# aig2_power_cpu.net
KiCad netlist of a schematic drawn in Altium Designer
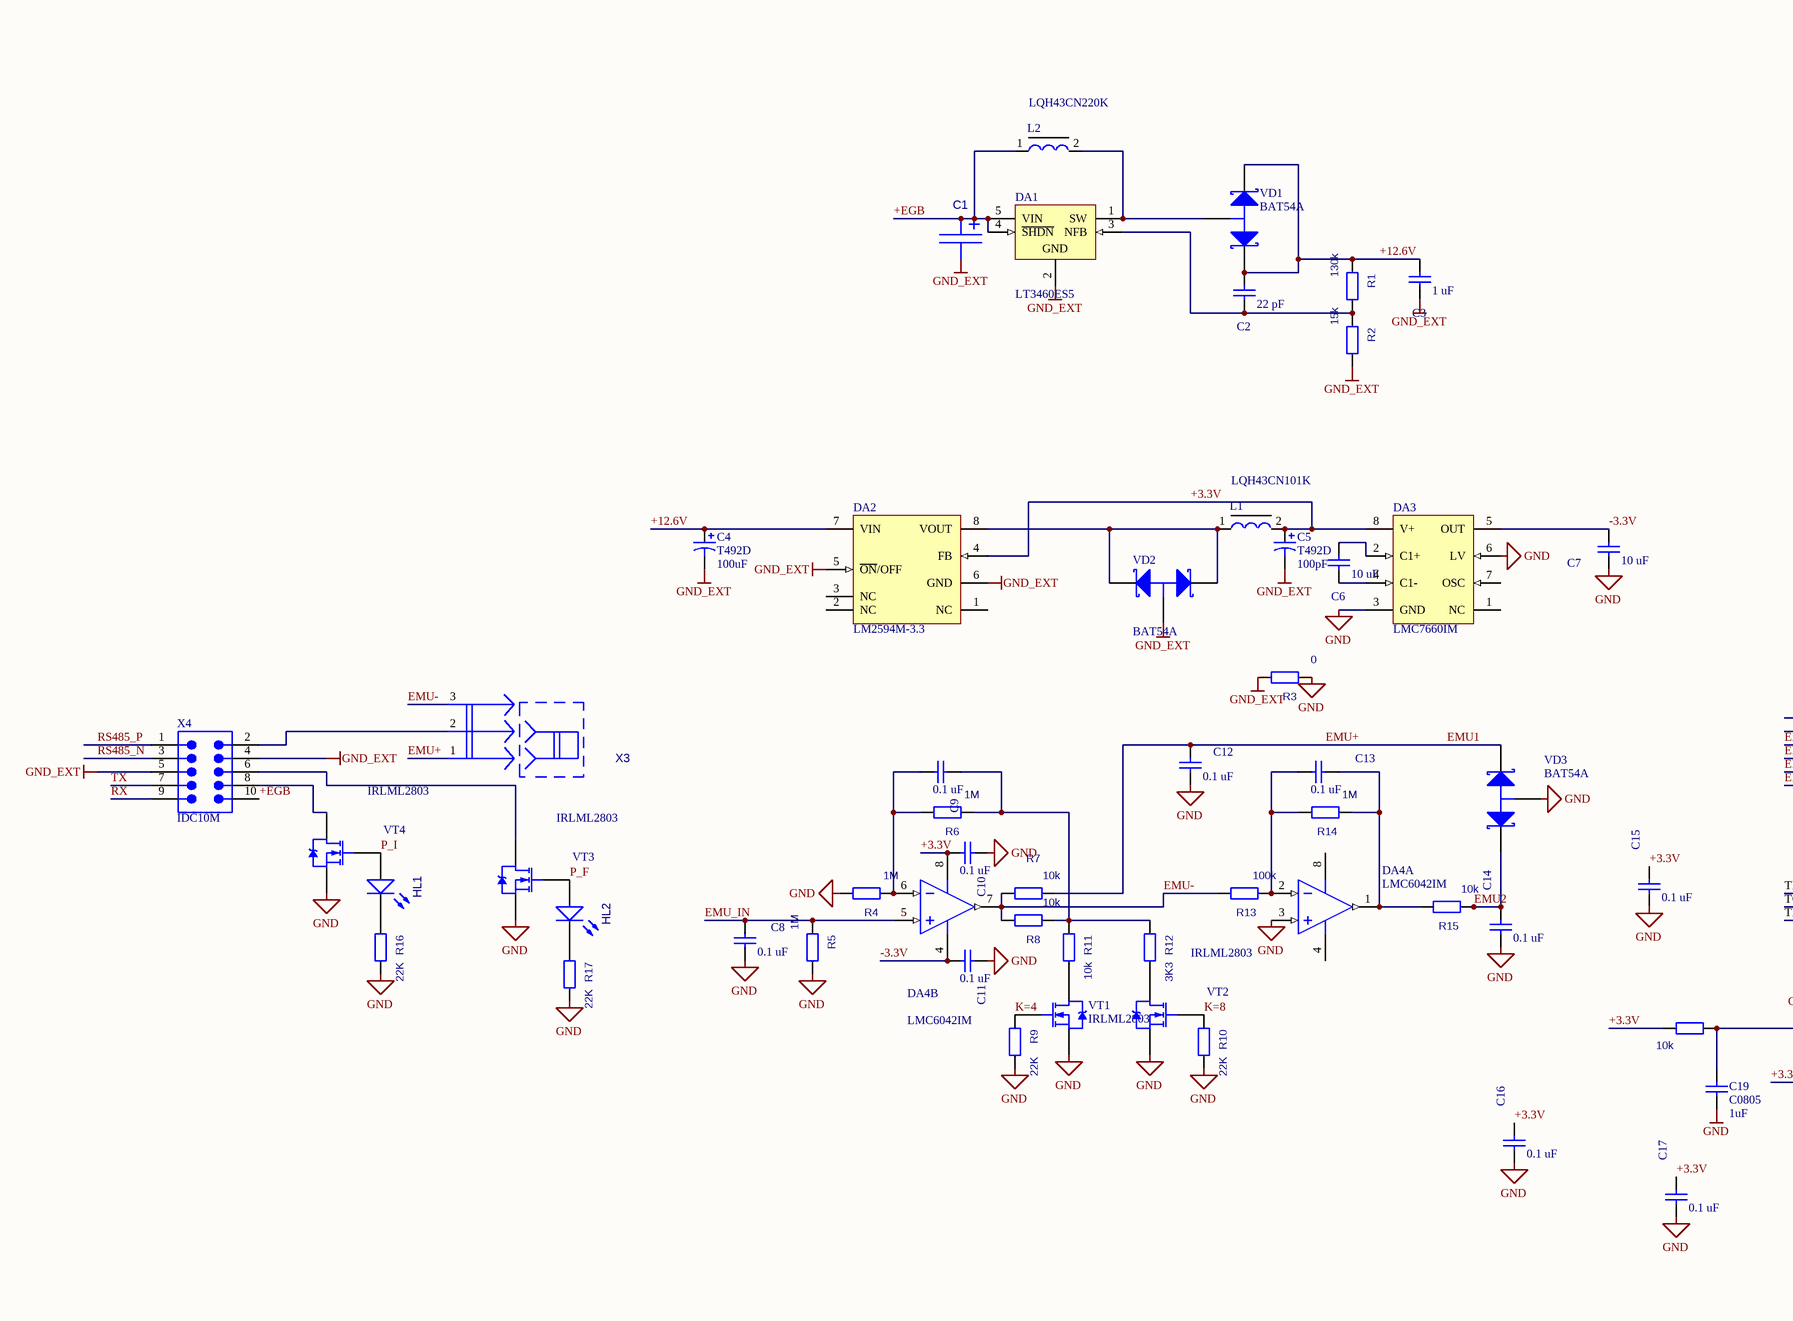
[diagram p0: aig2_power_cpu.SchDoc, left]
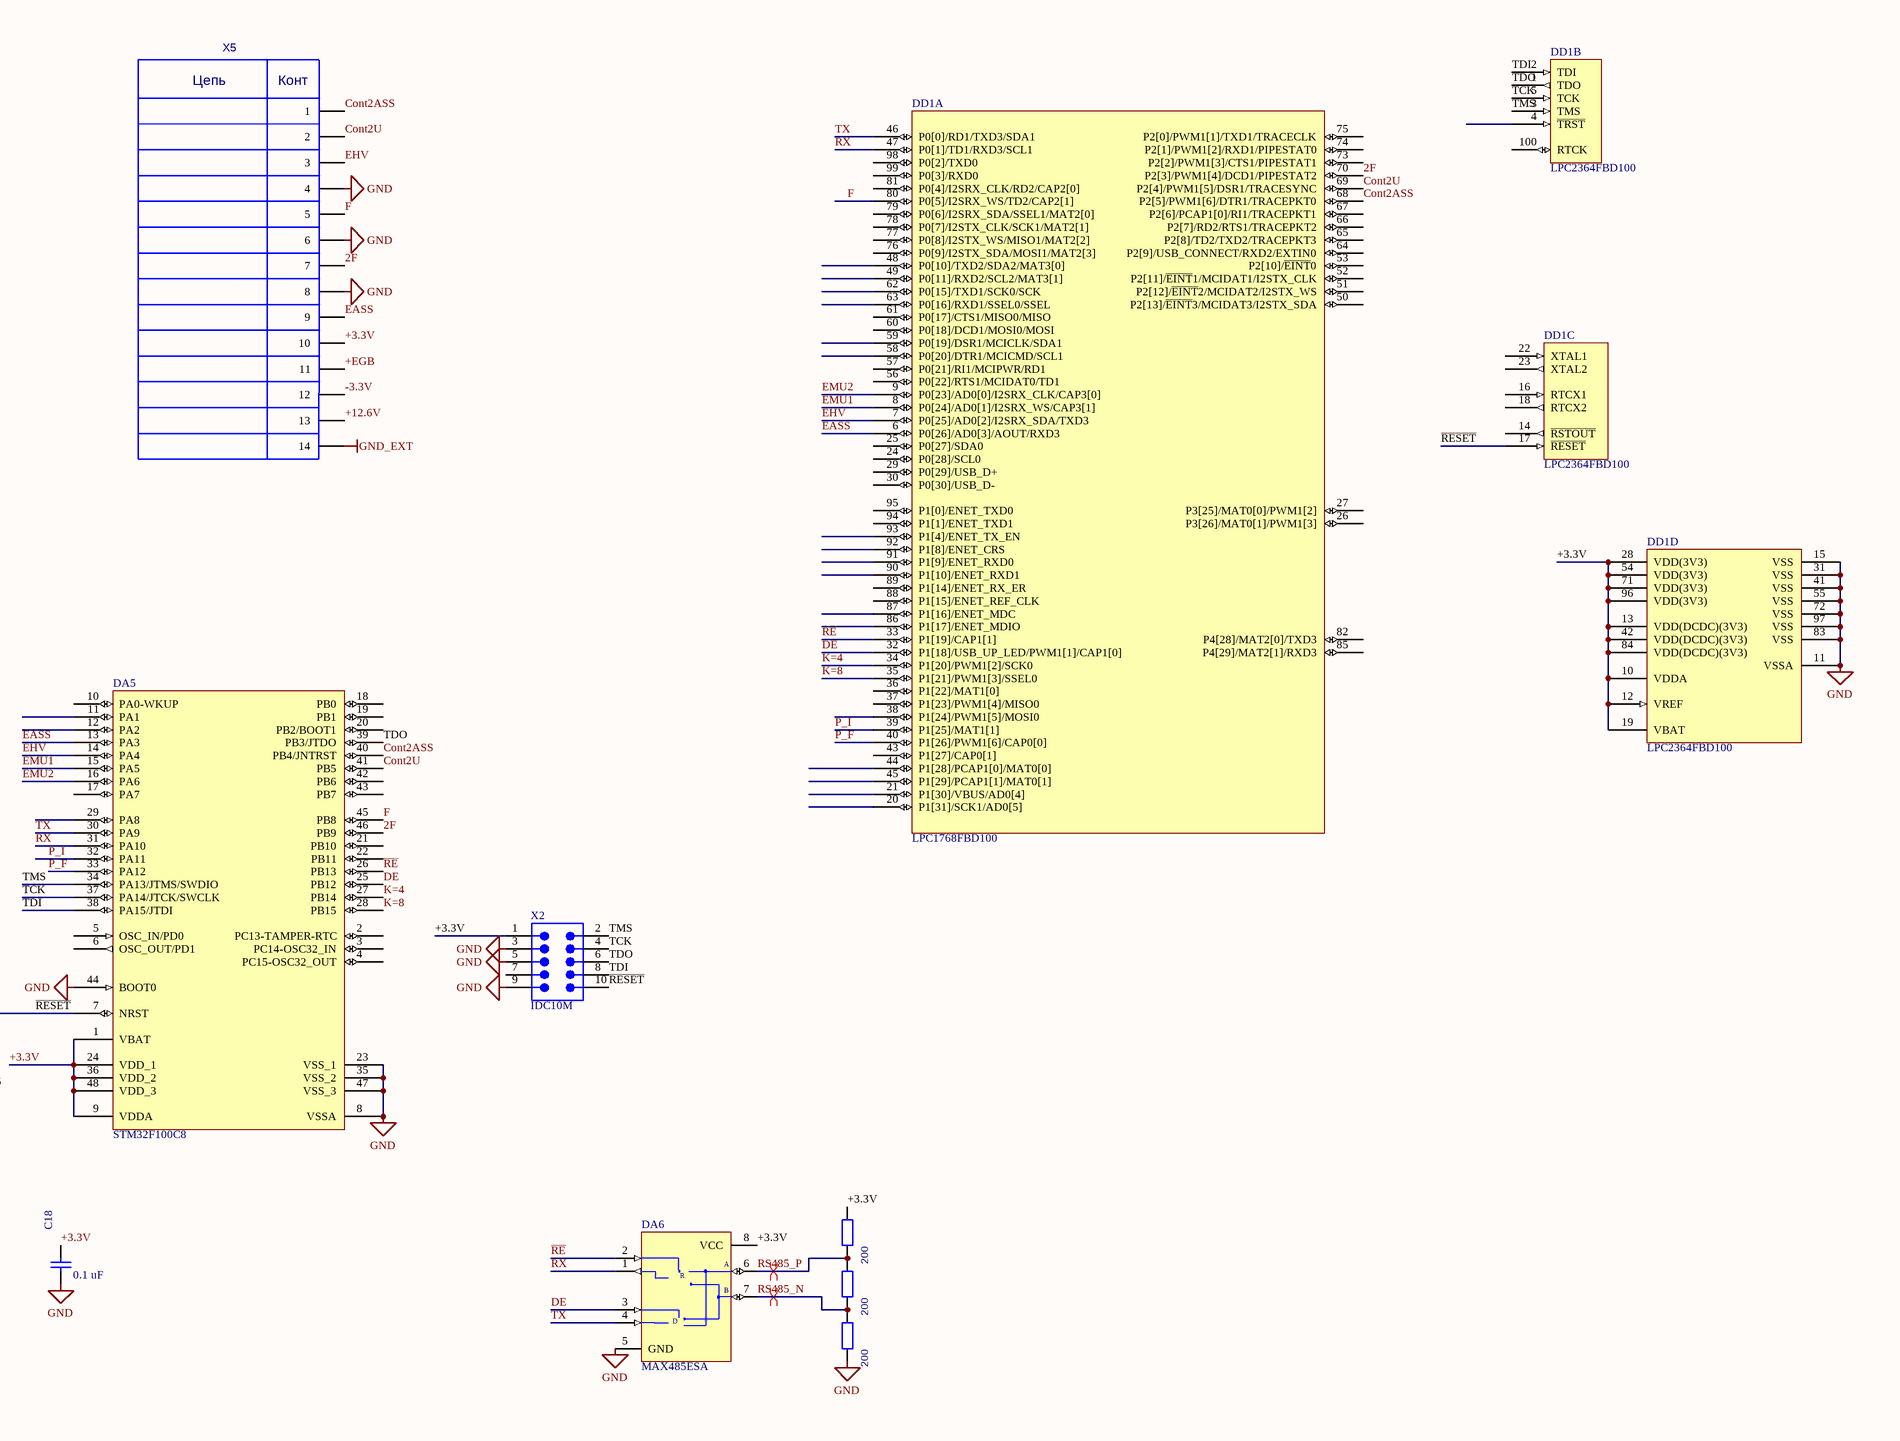
[diagram p1: aig2_power_cpu.SchDoc, right]

(export (version "E")
  (design (tool "Eeschema 10.0.6"))
  (components
    (comp (ref "C1")
      (value "CAPASITOR A")
      (footprint "CAPASITOR A")
      (libsource (lib "MyElements") (part "CAPASITOR A"))
    )
    (comp (ref "C2")
      (value "22 pF")
      (footprint "CC0805")
      (description "Ceramic Chip Capacitor - Standard")
      (fields (field (name "Comment") "C0805") (field (name "PUBLISHER") "Altium Limited"))
      (libsource (lib "KEMET Chip Capacitor") (part "C0805"))
    )
    (comp (ref "C3")
      (value "1 uF")
      (footprint "CC0805")
      (description "Ceramic Chip Capacitor - Standard")
      (fields (field (name "Comment") "C0805") (field (name "PUBLISHER") "Altium Limited"))
      (libsource (lib "KEMET Chip Capacitor") (part "C0805"))
    )
    (comp (ref "C4")
      (value "T492D")
      (footprint "D")
      (description "Solid Tantalum Chip Capacitor, T492 Series - CWR11 Style Per Mil-PRF-55365/8")
      (fields (field (name "ALTIUM_VALUE") "100uF") (field (name "PUBLISHER") "Altium Limited"))
      (libsource (lib "KEMET Chip Capacitor") (part "T492D"))
    )
    (comp (ref "C5")
      (value "T492D")
      (footprint "D")
      (description "Solid Tantalum Chip Capacitor, T492 Series - CWR11 Style Per Mil-PRF-55365/8")
      (fields (field (name "ALTIUM_VALUE") "100pF") (field (name "PUBLISHER") "Altium Limited"))
      (libsource (lib "KEMET Chip Capacitor") (part "T492D"))
    )
    (comp (ref "C6")
      (value "10 uF")
      (footprint "CC0805")
      (description "Ceramic Chip Capacitor - Standard")
      (fields (field (name "Comment") "C0805") (field (name "PUBLISHER") "Altium Limited"))
      (libsource (lib "KEMET Chip Capacitor") (part "C0805"))
    )
    (comp (ref "C7")
      (value "10 uF")
      (footprint "CC0805")
      (description "Ceramic Chip Capacitor - Standard")
      (fields (field (name "Comment") "C0805") (field (name "PUBLISHER") "Altium Limited"))
      (libsource (lib "KEMET Chip Capacitor") (part "C0805"))
    )
    (comp (ref "C8")
      (value "0.1 uF")
      (footprint "CC0805")
      (description "Ceramic Chip Capacitor - Standard")
      (fields (field (name "Comment") "C0805") (field (name "PUBLISHER") "Altium Limited"))
      (libsource (lib "KEMET Chip Capacitor") (part "C0805"))
    )
    (comp (ref "C9")
      (value "0.1 uF")
      (footprint "CC0805")
      (description "Ceramic Chip Capacitor - Standard")
      (fields (field (name "Comment") "C0805") (field (name "PUBLISHER") "Altium Limited"))
      (libsource (lib "KEMET Chip Capacitor") (part "C0805"))
    )
    (comp (ref "C10")
      (value "0.1 uF")
      (footprint "CC0805")
      (description "Ceramic Chip Capacitor - Standard")
      (fields (field (name "Comment") "C0805") (field (name "PUBLISHER") "Altium Limited"))
      (libsource (lib "KEMET Chip Capacitor") (part "C0805"))
    )
    (comp (ref "C11")
      (value "0.1 uF")
      (footprint "CC0805")
      (description "Ceramic Chip Capacitor - Standard")
      (fields (field (name "Comment") "C0805") (field (name "PUBLISHER") "Altium Limited"))
      (libsource (lib "KEMET Chip Capacitor") (part "C0805"))
    )
    (comp (ref "C12")
      (value "0.1 uF")
      (footprint "CC0805")
      (description "Ceramic Chip Capacitor - Standard")
      (fields (field (name "Comment") "C0805") (field (name "PUBLISHER") "Altium Limited"))
      (libsource (lib "KEMET Chip Capacitor") (part "C0805"))
    )
    (comp (ref "C13")
      (value "0.1 uF")
      (footprint "CC0805")
      (description "Ceramic Chip Capacitor - Standard")
      (fields (field (name "Comment") "C0805") (field (name "PUBLISHER") "Altium Limited"))
      (libsource (lib "KEMET Chip Capacitor") (part "C0805"))
    )
    (comp (ref "C14")
      (value "0.1 uF")
      (footprint "CC0805")
      (description "Ceramic Chip Capacitor - Standard")
      (fields (field (name "Comment") "C0805") (field (name "PUBLISHER") "Altium Limited"))
      (libsource (lib "KEMET Chip Capacitor") (part "C0805"))
    )
    (comp (ref "C15")
      (value "0.1 uF")
      (footprint "CC0805")
      (description "Ceramic Chip Capacitor - Standard")
      (fields (field (name "Comment") "C0805") (field (name "PUBLISHER") "Altium Limited"))
      (libsource (lib "KEMET Chip Capacitor") (part "C0805"))
    )
    (comp (ref "C16")
      (value "0.1 uF")
      (footprint "CC0805")
      (description "Ceramic Chip Capacitor - Standard")
      (fields (field (name "Comment") "C0805") (field (name "PUBLISHER") "Altium Limited"))
      (libsource (lib "KEMET Chip Capacitor") (part "C0805"))
    )
    (comp (ref "C17")
      (value "0.1 uF")
      (footprint "CC0805")
      (description "Ceramic Chip Capacitor - Standard")
      (fields (field (name "Comment") "C0805") (field (name "PUBLISHER") "Altium Limited"))
      (libsource (lib "KEMET Chip Capacitor") (part "C0805"))
    )
    (comp (ref "C18")
      (value "0.1 uF")
      (footprint "CC0805")
      (description "Ceramic Chip Capacitor - Standard")
      (fields (field (name "Comment") "C0805") (field (name "PUBLISHER") "Altium Limited"))
      (libsource (lib "KEMET Chip Capacitor") (part "C0805"))
    )
    (comp (ref "C19")
      (value "C0805")
      (footprint "CC0805")
      (description "Ceramic Chip Capacitor - Standard")
      (fields (field (name "ALTIUM_VALUE") "1uF") (field (name "PUBLISHER") "Altium Limited"))
      (libsource (lib "KEMET Chip Capacitor") (part "C0805"))
    )
    (comp (ref "DA1")
      (value "LT3460ES5")
      (footprint "S5-T_N")
      (description "2.2MHz Inverting Current Mode DC/DC Converter")
      (fields (field (name "PUBLISHER") "Altium Limited"))
      (libsource (lib "LT Power Mgt DC-DC Converter") (part "LT1931AES5"))
    )
    (comp (ref "DA2")
      (value "LM2594M-3.3")
      (footprint "M08A_N")
      (description "SIMPLE SWITCHER Power Converter 150 KHz 0.5A Step-Down Voltage Regulator")
      (fields
        (field (name "MANUFACTURER") "National Semiconductor")
        (field (name "DIGIKEYPARTNUMBER") "LM2594M-3.3-ND")
        (field (name "PUBLISHER") "Altium Limited")
      )
      (libsource (lib "NSC Switcher") (part "LM2594M-3.3"))
    )
    (comp (ref "DA3")
      (value "LMC7660IM")
      (footprint "M08A_N")
      (description "Switched Capacitor Voltage Converter")
      (fields
        (field (name "MANUFACTURER") "National Semiconductor")
        (field (name "DIGIKEYPARTNUMBER") "LMC7660IM-ND")
        (field (name "PUBLISHER") "Altium Limited")
      )
      (libsource (lib "NSC Switch Caps") (part "LMC7660IM"))
    )
    (comp (ref "DA4")
      (value "LMC6042IM")
      (footprint "M08A_N")
      (description "CMOS Dual Micropower Operational Amplifier")
      (fields
        (field (name "MANUFACTURER") "National Semiconductor")
        (field (name "DIGIKEYPARTNUMBER") "LMC6042IM-ND")
        (field (name "PUBLISHER") "Altium Limited")
      )
      (libsource (lib "NSC Amplifier") (part "LMC6042IM"))
    )
    (comp (ref "DA5")
      (value "STM32F100C8")
      (footprint "LQFP48_N")
      (description "STM32 ARM-based 32-bit MCU with 32 Kbytes Flash, 48-pin LQFP, Industrial Temperature")
      (fields (field (name "PUBLISHER") "Altium Limited"))
      (libsource (lib "ST Microcontroller 32-Bit STM32") (part "STM32F101C6T6"))
    )
    (comp (ref "DA6")
      (value "MAX485ESA")
      (footprint "NSO8_N")
      (description "Low-Power, Slew-Rate-Limited RS-485/RS-422 Transceiver")
      (fields (field (name "PUBLISHER") "Altium Limited"))
      (libsource (lib "Maxim Communication Transceiver") (part "MAX485ESA"))
    )
    (comp (ref "DD1")
      (value "LPC1768FBD100")
      (footprint "SOT407-1_N")
      (description "ARM7 16/32-Bit Microcontroller, 128KB Flash, 34KB RAM, 4 Channel CAN, 100-Lead LQFP")
      (fields (field (name "PUBLISHER") "Altium Limited"))
      (libsource (lib "NXP LPC2000") (part "LPC2364FBD100"))
    )
    (comp (ref "HL1") (value "LED0805") (footprint "led1206") (libsource (lib "MyElements") (part "LED0805")))
    (comp (ref "HL2") (value "LED0805") (footprint "led1206") (libsource (lib "MyElements") (part "LED0805")))
    (comp (ref "L1")
      (value "LQH43CN101K")
      (footprint "1812")
      (description "Дроссель")
      (libsource (lib "lgar") (part "CDRH127"))
    )
    (comp (ref "L2")
      (value "LQH43CN220K")
      (footprint "1812")
      (description "Дроссель")
      (libsource (lib "lgar") (part "CDRH127"))
    )
    (comp (ref "R1")
      (value "130k")
      (footprint "RR0805")
      (description "R_0805")
      (libsource (lib "*") (part "R_0805"))
    )
    (comp (ref "R2")
      (value "15k")
      (footprint "RR0805")
      (description "R_0805")
      (libsource (lib "*") (part "R_0805"))
    )
    (comp (ref "R3")
      (value "0")
      (footprint "RR0805")
      (description "R_0805")
      (libsource (lib "*") (part "R_0805"))
    )
    (comp (ref "R4")
      (value "1M")
      (footprint "RR0805")
      (description "R_0805")
      (libsource (lib "*") (part "R_0805"))
    )
    (comp (ref "R5")
      (value "1M")
      (footprint "RR0805")
      (description "R_0805")
      (libsource (lib "*") (part "R_0805"))
    )
    (comp (ref "R6")
      (value "1M")
      (footprint "RR0805")
      (description "R_0805")
      (libsource (lib "*") (part "R_0805"))
    )
    (comp (ref "R7")
      (value "10k")
      (footprint "RR0805")
      (description "R_0805")
      (libsource (lib "*") (part "R_0805"))
    )
    (comp (ref "R8")
      (value "10k")
      (footprint "RR0805")
      (description "R_0805")
      (libsource (lib "*") (part "R_0805"))
    )
    (comp (ref "R9")
      (value "22K")
      (footprint "RR0805")
      (description "R_0805")
      (libsource (lib "*") (part "R_0805"))
    )
    (comp (ref "R10")
      (value "22K")
      (footprint "RR0805")
      (description "R_0805")
      (libsource (lib "*") (part "R_0805"))
    )
    (comp (ref "R11")
      (value "10k")
      (footprint "RR0805")
      (description "R_0805")
      (libsource (lib "*") (part "R_0805"))
    )
    (comp (ref "R12")
      (value "3K3")
      (footprint "RR0805")
      (description "R_0805")
      (libsource (lib "*") (part "R_0805"))
    )
    (comp (ref "R13")
      (value "100k")
      (footprint "RR0805")
      (description "R_0805")
      (libsource (lib "*") (part "R_0805"))
    )
    (comp (ref "R14")
      (value "1M")
      (footprint "RR0805")
      (description "R_0805")
      (libsource (lib "*") (part "R_0805"))
    )
    (comp (ref "R15")
      (value "10k")
      (footprint "RR0805")
      (description "R_0805")
      (libsource (lib "*") (part "R_0805"))
    )
    (comp (ref "R16")
      (value "22K")
      (footprint "RR0805")
      (description "R_0805")
      (libsource (lib "*") (part "R_0805"))
    )
    (comp (ref "R17")
      (value "22K")
      (footprint "RR0805")
      (description "R_0805")
      (libsource (lib "*") (part "R_0805"))
    )
    (comp (ref "R18")
      (value "10k")
      (footprint "RR0805")
      (description "R_0805")
      (libsource (lib "*") (part "R_0805"))
    )
    (comp (ref "R19")
      (value "200")
      (footprint "RR0805")
      (description "R_0805")
      (libsource (lib "*") (part "R_0805"))
    )
    (comp (ref "R20")
      (value "200")
      (footprint "RR0805")
      (description "R_0805")
      (libsource (lib "*") (part "R_0805"))
    )
    (comp (ref "R21")
      (value "200")
      (footprint "RR0805")
      (description "R_0805")
      (libsource (lib "*") (part "R_0805"))
    )
    (comp (ref "VD1")
      (value "BAT54A")
      (footprint "SOT23_N")
      (description "Schottky Barrier Double Diode")
      (fields (field (name "PUBLISHER") "Altium Limited"))
      (libsource (lib "Philips Discrete Diode - Schottky") (part "BAT54A"))
    )
    (comp (ref "VD2")
      (value "BAT54A")
      (footprint "SOT23_N")
      (description "Schottky Barrier Double Diode")
      (fields (field (name "PUBLISHER") "Altium Limited"))
      (libsource (lib "Philips Discrete Diode - Schottky") (part "BAT54A"))
    )
    (comp (ref "VD3")
      (value "BAT54A")
      (footprint "SOT23_N")
      (description "Schottky Barrier Double Diode")
      (fields (field (name "PUBLISHER") "Altium Limited"))
      (libsource (lib "Philips Discrete Diode - Schottky") (part "BAT54A"))
    )
    (comp (ref "VT1")
      (value "IRLML2803")
      (footprint "SOT-23")
      (description "HEXFET Power MOSFET")
      (fields (field (name "PUBLISHER") "Altium Limited"))
      (libsource (lib "IR Discrete MOSFET - Power") (part "IRLML2803"))
    )
    (comp (ref "VT2")
      (value "IRLML2803")
      (footprint "SOT-23")
      (description "HEXFET Power MOSFET")
      (fields (field (name "PUBLISHER") "Altium Limited"))
      (libsource (lib "IR Discrete MOSFET - Power") (part "IRLML2803"))
    )
    (comp (ref "VT3")
      (value "IRLML2803")
      (footprint "SOT-23")
      (description "HEXFET Power MOSFET")
      (fields (field (name "PUBLISHER") "Altium Limited"))
      (libsource (lib "IR Discrete MOSFET - Power") (part "IRLML2803"))
    )
    (comp (ref "VT4")
      (value "IRLML2803")
      (footprint "SOT-23")
      (description "HEXFET Power MOSFET")
      (fields (field (name "PUBLISHER") "Altium Limited"))
      (libsource (lib "IR Discrete MOSFET - Power") (part "IRLML2803"))
    )
    (comp (ref "X2")
      (value "IDC10M")
      (footprint "idc10_2")
      (description "Flat Cable Connector (IDC), PCB Transition Connector, 2 Rows, Solder Pin, 10 Contacts")
      (fields (field (name "PUBLISHER") "Altium Limited"))
      (libsource (lib "HARTING IDC 2.54mm Pitch") (part "09 18 110 9621"))
    )
    (comp (ref "X3") (value "JP3") (footprint "PLS-3 2.54") (libsource (lib "MyElements") (part "JP3")))
    (comp (ref "X4")
      (value "IDC10M")
      (footprint "idc10_2")
      (description "Flat Cable Connector (IDC), PCB Transition Connector, 2 Rows, Solder Pin, 10 Contacts")
      (fields (field (name "PUBLISHER") "Altium Limited"))
      (libsource (lib "HARTING IDC 2.54mm Pitch") (part "09 18 110 9621"))
    )
    (comp (ref "X5") (value "IDC14M") (footprint "IDC14M") (libsource (lib "MyElements") (part "IDC14M")))
  )
  (nets
    (net (code "1") (name "/+3.3V") (class "Default")
      (node (ref "C10") (pin "1") (pinfunction "1_1") (pintype "passive"))
      (node (ref "C15") (pin "2") (pinfunction "2_2") (pintype "passive"))
      (node (ref "C16") (pin "2") (pinfunction "2_2") (pintype "passive"))
      (node (ref "C17") (pin "2") (pinfunction "2_2") (pintype "passive"))
      (node (ref "C18") (pin "2") (pinfunction "2_2") (pintype "passive"))
      (node (ref "C5") (pin "1") (pinfunction "1_1") (pintype "passive"))
      (node (ref "DA2") (pin "4") (pinfunction "FB_4") (pintype "input"))
      (node (ref "DA3") (pin "8") (pinfunction "V+_8") (pintype "power_in"))
      (node (ref "DA4") (pin "8") (pinfunction "V+_8") (pintype "power_in"))
      (node (ref "DA5") (pin "1") (pinfunction "VBAT_1") (pintype "power_in"))
      (node (ref "DA5") (pin "24") (pinfunction "VDD_1_24") (pintype "power_in"))
      (node (ref "DA5") (pin "36") (pinfunction "VDD_2_36") (pintype "power_in"))
      (node (ref "DA5") (pin "48") (pinfunction "VDD_3_48") (pintype "power_in"))
      (node (ref "DA5") (pin "9") (pinfunction "VDDA_9") (pintype "power_in"))
      (node (ref "DA6") (pin "8") (pinfunction "VCC_8") (pintype "power_in"))
      (node (ref "DD1") (pin "10") (pinfunction "VDDA_10") (pintype "power_in"))
      (node (ref "DD1") (pin "12") (pinfunction "VREF_12") (pintype "input"))
      (node (ref "DD1") (pin "13") (pinfunction "VDD(DCDC)(3V3)_13") (pintype "power_in"))
      (node (ref "DD1") (pin "19") (pinfunction "VBAT_19") (pintype "power_in"))
      (node (ref "DD1") (pin "28") (pinfunction "VDD(3V3)_28") (pintype "power_in"))
      (node (ref "DD1") (pin "42") (pinfunction "VDD(DCDC)(3V3)_42") (pintype "power_in"))
      (node (ref "DD1") (pin "54") (pinfunction "VDD(3V3)_54") (pintype "power_in"))
      (node (ref "DD1") (pin "71") (pinfunction "VDD(3V3)_71") (pintype "power_in"))
      (node (ref "DD1") (pin "84") (pinfunction "VDD(DCDC)(3V3)_84") (pintype "power_in"))
      (node (ref "DD1") (pin "96") (pinfunction "VDD(3V3)_96") (pintype "power_in"))
      (node (ref "L1") (pin "2") (pinfunction "2_2") (pintype "passive"))
      (node (ref "R18") (pin "1") (pintype "passive"))
      (node (ref "R19") (pin "2") (pintype "passive"))
      (node (ref "X2") (pin "1") (pinfunction "1_1") (pintype "passive"))
      (node (ref "X5") (pin "10") (pinfunction "10_10") (pintype "passive"))
    )
    (net (code "2") (name "/+12.6V") (class "Default")
      (node (ref "C2") (pin "1") (pinfunction "1_1") (pintype "passive"))
      (node (ref "C3") (pin "1") (pinfunction "1_1") (pintype "passive"))
      (node (ref "C4") (pin "1") (pinfunction "1_1") (pintype "passive"))
      (node (ref "DA2") (pin "7") (pinfunction "VIN_7") (pintype "power_in"))
      (node (ref "R1") (pin "1") (pintype "passive"))
      (node (ref "VD1") (pin "1") (pinfunction "K1_1") (pintype "passive"))
      (node (ref "VD1") (pin "2") (pinfunction "K2_2") (pintype "passive"))
      (node (ref "X5") (pin "13") (pinfunction "13_13") (pintype "passive"))
    )
    (net (code "3") (name "/+EGB") (class "Default")
      (node (ref "C1") (pin "1") (pinfunction "i/o_1") (pintype "passive"))
      (node (ref "DA1") (pin "4") (pinfunction "~{SHDN}_4") (pintype "input"))
      (node (ref "DA1") (pin "5") (pinfunction "VIN_5") (pintype "power_in"))
      (node (ref "L2") (pin "1") (pinfunction "1_1") (pintype "passive"))
      (node (ref "X4") (pin "10") (pinfunction "10_10") (pintype "passive"))
      (node (ref "X5") (pin "11") (pinfunction "11_11") (pintype "passive"))
    )
    (net (code "4") (name "/-3.3V") (class "Default")
      (node (ref "C11") (pin "1") (pinfunction "1_1") (pintype "passive"))
      (node (ref "C7") (pin "1") (pinfunction "1_1") (pintype "passive"))
      (node (ref "DA3") (pin "5") (pinfunction "OUT_5") (pintype "power_in"))
      (node (ref "DA4") (pin "4") (pinfunction "V-_4") (pintype "power_in"))
      (node (ref "X5") (pin "12") (pinfunction "12_12") (pintype "passive"))
    )
    (net (code "5") (name "/2F") (class "Default")
      (node (ref "DA5") (pin "46") (pinfunction "PB9_46") (pintype "bidirectional"))
      (node (ref "DD1") (pin "70") (pinfunction "P2[3]/PWM1[4]/DCD1/PIPESTAT2_70") (pintype "bidirectional"))
      (node (ref "X5") (pin "7") (pinfunction "7_7") (pintype "passive"))
    )
    (net (code "6") (name "/Cont2ASS") (class "Default")
      (node (ref "DA5") (pin "40") (pinfunction "PB4/JNTRST_40") (pintype "bidirectional"))
      (node (ref "DD1") (pin "68") (pinfunction "P2[5]/PWM1[6]/DTR1/TRACEPKT0_68") (pintype "bidirectional"))
      (node (ref "X5") (pin "1") (pinfunction "1_1") (pintype "passive"))
    )
    (net (code "7") (name "/Cont2U") (class "Default")
      (node (ref "DA5") (pin "41") (pinfunction "PB5_41") (pintype "bidirectional"))
      (node (ref "DD1") (pin "69") (pinfunction "P2[4]/PWM1[5]/DSR1/TRACESYNC_69") (pintype "bidirectional"))
      (node (ref "X5") (pin "2") (pinfunction "2_2") (pintype "passive"))
    )
    (net (code "8") (name "/DE") (class "Default")
      (node (ref "DA5") (pin "25") (pinfunction "PB12_25") (pintype "bidirectional"))
      (node (ref "DA6") (pin "3") (pinfunction "DE_3") (pintype "input"))
      (node (ref "DD1") (pin "32") (pinfunction "P1[18]/USB_UP_LED/PWM1[1]/CAP1[0]_32") (pintype "bidirectional"))
    )
    (net (code "9") (name "/EASS") (class "Default")
      (node (ref "DA5") (pin "13") (pinfunction "PA3_13") (pintype "bidirectional"))
      (node (ref "DD1") (pin "6") (pinfunction "P0[26]/AD0[3]/AOUT/RXD3_6") (pintype "bidirectional"))
      (node (ref "X5") (pin "9") (pinfunction "9_9") (pintype "passive"))
    )
    (net (code "10") (name "/EHV") (class "Default")
      (node (ref "DA5") (pin "14") (pinfunction "PA4_14") (pintype "bidirectional"))
      (node (ref "DD1") (pin "7") (pinfunction "P0[25]/AD0[2]/I2SRX_SDA/TXD3_7") (pintype "bidirectional"))
      (node (ref "X5") (pin "3") (pinfunction "3_3") (pintype "passive"))
    )
    (net (code "11") (name "/EMU+") (class "Default")
      (node (ref "C12") (pin "2") (pinfunction "2_2") (pintype "passive"))
      (node (ref "DA5") (pin "15") (pinfunction "PA5_15") (pintype "bidirectional"))
      (node (ref "DD1") (pin "8") (pinfunction "P0[24]/AD0[1]/I2SRX_WS/CAP3[1]_8") (pintype "bidirectional"))
      (node (ref "R7") (pin "1") (pintype "passive"))
      (node (ref "VD3") (pin "1") (pinfunction "K1_1") (pintype "passive"))
      (node (ref "X3") (pin "1") (pinfunction "I/O1_1") (pintype "passive"))
    )
    (net (code "12") (name "/EMU-") (class "Default")
      (node (ref "DA4") (pin "7") (pinfunction "OUTB_7") (pintype "output"))
      (node (ref "R13") (pin "2") (pintype "passive"))
      (node (ref "R7") (pin "2") (pintype "passive"))
      (node (ref "R8") (pin "2") (pintype "passive"))
      (node (ref "X3") (pin "3") (pinfunction "I/O3_3") (pintype "passive"))
    )
    (net (code "13") (name "/EMU2") (class "Default")
      (node (ref "C14") (pin "2") (pinfunction "2_2") (pintype "passive"))
      (node (ref "DA5") (pin "16") (pinfunction "PA6_16") (pintype "bidirectional"))
      (node (ref "DD1") (pin "9") (pinfunction "P0[23]/AD0[0]/I2SRX_CLK/CAP3[0]_9") (pintype "bidirectional"))
      (node (ref "R15") (pin "1") (pintype "passive"))
      (node (ref "VD3") (pin "2") (pinfunction "K2_2") (pintype "passive"))
    )
    (net (code "14") (name "/EMU_IN") (class "Default")
      (node (ref "C8") (pin "2") (pinfunction "2_2") (pintype "passive"))
      (node (ref "DA4") (pin "5") (pinfunction "INB+_5") (pintype "input"))
      (node (ref "R5") (pin "1") (pintype "passive"))
    )
    (net (code "15") (name "/F") (class "Default")
      (node (ref "DA5") (pin "45") (pinfunction "PB8_45") (pintype "bidirectional"))
      (node (ref "DD1") (pin "80") (pinfunction "P0[5]/I2SRX_WS/TD2/CAP2[1]_80") (pintype "bidirectional"))
      (node (ref "X5") (pin "5") (pinfunction "5_5") (pintype "passive"))
    )
    (net (code "16") (name "/K=4") (class "Default")
      (node (ref "DA5") (pin "27") (pinfunction "PB14_27") (pintype "bidirectional"))
      (node (ref "DD1") (pin "34") (pinfunction "P1[20]/PWM1[2]/SCK0_34") (pintype "bidirectional"))
      (node (ref "R9") (pin "1") (pintype "passive"))
      (node (ref "VT1") (pin "1") (pinfunction "G_1") (pintype "passive"))
    )
    (net (code "17") (name "/K=8") (class "Default")
      (node (ref "DA5") (pin "28") (pinfunction "PB15_28") (pintype "bidirectional"))
      (node (ref "DD1") (pin "35") (pinfunction "P1[21]/PWM1[3]/SSEL0_35") (pintype "bidirectional"))
      (node (ref "R10") (pin "1") (pintype "passive"))
      (node (ref "VT2") (pin "1") (pinfunction "G_1") (pintype "passive"))
    )
    (net (code "18") (name "/P_F") (class "Default")
      (node (ref "DA5") (pin "33") (pinfunction "PA12_33") (pintype "bidirectional"))
      (node (ref "DD1") (pin "40") (pinfunction "P1[26]/PWM1[6]/CAP0[0]_40") (pintype "bidirectional"))
      (node (ref "HL2") (pin "1") (pinfunction "A_1") (pintype "passive"))
      (node (ref "VT3") (pin "1") (pinfunction "G_1") (pintype "passive"))
    )
    (net (code "19") (name "/P_I") (class "Default")
      (node (ref "DA5") (pin "32") (pinfunction "PA11_32") (pintype "bidirectional"))
      (node (ref "DD1") (pin "39") (pinfunction "P1[25]/MAT1[1]_39") (pintype "bidirectional"))
      (node (ref "HL1") (pin "1") (pinfunction "A_1") (pintype "passive"))
      (node (ref "VT4") (pin "1") (pinfunction "G_1") (pintype "passive"))
    )
    (net (code "20") (name "/RS485_N") (class "Default")
      (node (ref "DA6") (pin "7") (pinfunction "B_7") (pintype "bidirectional"))
      (node (ref "R20") (pin "1") (pintype "passive"))
      (node (ref "R21") (pin "2") (pintype "passive"))
      (node (ref "X4") (pin "3") (pinfunction "3_3") (pintype "passive"))
    )
    (net (code "21") (name "/RS485_P") (class "Default")
      (node (ref "DA6") (pin "6") (pinfunction "A_6") (pintype "bidirectional"))
      (node (ref "R19") (pin "1") (pintype "passive"))
      (node (ref "R20") (pin "2") (pintype "passive"))
      (node (ref "X4") (pin "1") (pinfunction "1_1") (pintype "passive"))
    )
    (net (code "22") (name "/RX") (class "Default")
      (node (ref "DA5") (pin "31") (pinfunction "PA10_31") (pintype "bidirectional"))
      (node (ref "DA6") (pin "1") (pinfunction "RO_1") (pintype "output"))
      (node (ref "DD1") (pin "47") (pinfunction "P0[1]/TD1/RXD3/SCL1_47") (pintype "bidirectional"))
      (node (ref "X4") (pin "9") (pinfunction "9_9") (pintype "passive"))
    )
    (net (code "23") (name "/TCK") (class "Default")
      (node (ref "DA5") (pin "37") (pinfunction "PA14/JTCK/SWCLK_37") (pintype "bidirectional"))
      (node (ref "DD1") (pin "5") (pinfunction "TCK_5") (pintype "input"))
      (node (ref "X2") (pin "4") (pinfunction "4_4") (pintype "passive"))
    )
    (net (code "24") (name "/TDI") (class "Default")
      (node (ref "DA5") (pin "38") (pinfunction "PA15/JTDI_38") (pintype "bidirectional"))
      (node (ref "DD1") (pin "2") (pinfunction "TDI_2") (pintype "input"))
      (node (ref "X2") (pin "8") (pinfunction "8_8") (pintype "passive"))
    )
    (net (code "25") (name "/TDO") (class "Default")
      (node (ref "DA5") (pin "39") (pinfunction "PB3/JTDO_39") (pintype "bidirectional"))
      (node (ref "DD1") (pin "1") (pinfunction "TDO_1") (pintype "output"))
      (node (ref "X2") (pin "6") (pinfunction "6_6") (pintype "passive"))
    )
    (net (code "26") (name "/TMS") (class "Default")
      (node (ref "DA5") (pin "34") (pinfunction "PA13/JTMS/SWDIO_34") (pintype "bidirectional"))
      (node (ref "DD1") (pin "3") (pinfunction "TMS_3") (pintype "input"))
      (node (ref "X2") (pin "2") (pinfunction "2_2") (pintype "passive"))
    )
    (net (code "27") (name "/TX") (class "Default")
      (node (ref "DA5") (pin "30") (pinfunction "PA9_30") (pintype "bidirectional"))
      (node (ref "DA6") (pin "4") (pinfunction "DI_4") (pintype "input"))
      (node (ref "DD1") (pin "46") (pinfunction "P0[0]/RD1/TXD3/SDA1_46") (pintype "bidirectional"))
      (node (ref "X4") (pin "7") (pinfunction "7_7") (pintype "passive"))
    )
    (net (code "28") (name "/~{RESET}") (class "Default")
      (node (ref "C19") (pin "2") (pinfunction "2_2") (pintype "passive"))
      (node (ref "DA5") (pin "7") (pinfunction "NRST_7") (pintype "bidirectional"))
      (node (ref "DD1") (pin "17") (pinfunction "~{RESET}_17") (pintype "input"))
      (node (ref "R18") (pin "2") (pintype "passive"))
      (node (ref "X2") (pin "10") (pinfunction "10_10") (pintype "passive"))
    )
    (net (code "29") (name "/~{RE}") (class "Default")
      (node (ref "DA5") (pin "26") (pinfunction "PB13_26") (pintype "bidirectional"))
      (node (ref "DA6") (pin "2") (pinfunction "~{RE}_2") (pintype "input"))
      (node (ref "DD1") (pin "33") (pinfunction "P1[19]/CAP1[1]_33") (pintype "bidirectional"))
    )
    (net (code "30") (name "GND") (class "Default")
      (node (ref "C10") (pin "2") (pinfunction "2_2") (pintype "passive"))
      (node (ref "C11") (pin "2") (pinfunction "2_2") (pintype "passive"))
      (node (ref "C12") (pin "1") (pinfunction "1_1") (pintype "passive"))
      (node (ref "C14") (pin "1") (pinfunction "1_1") (pintype "passive"))
      (node (ref "C15") (pin "1") (pinfunction "1_1") (pintype "passive"))
      (node (ref "C16") (pin "1") (pinfunction "1_1") (pintype "passive"))
      (node (ref "C17") (pin "1") (pinfunction "1_1") (pintype "passive"))
      (node (ref "C18") (pin "1") (pinfunction "1_1") (pintype "passive"))
      (node (ref "C19") (pin "1") (pinfunction "1_1") (pintype "passive"))
      (node (ref "C7") (pin "2") (pinfunction "2_2") (pintype "passive"))
      (node (ref "C8") (pin "1") (pinfunction "1_1") (pintype "passive"))
      (node (ref "DA3") (pin "3") (pinfunction "GND_3") (pintype "power_in"))
      (node (ref "DA3") (pin "6") (pinfunction "LV_6") (pintype "input"))
      (node (ref "DA4") (pin "3") (pinfunction "INA+_3") (pintype "input"))
      (node (ref "DA5") (pin "23") (pinfunction "VSS_1_23") (pintype "power_in"))
      (node (ref "DA5") (pin "35") (pinfunction "VSS_2_35") (pintype "power_in"))
      (node (ref "DA5") (pin "44") (pinfunction "BOOT0_44") (pintype "input"))
      (node (ref "DA5") (pin "47") (pinfunction "VSS_3_47") (pintype "power_in"))
      (node (ref "DA5") (pin "8") (pinfunction "VSSA_8") (pintype "power_in"))
      (node (ref "DA6") (pin "5") (pinfunction "GND_5") (pintype "power_in"))
      (node (ref "DD1") (pin "11") (pinfunction "VSSA_11") (pintype "power_in"))
      (node (ref "DD1") (pin "15") (pinfunction "VSS_15") (pintype "power_in"))
      (node (ref "DD1") (pin "31") (pinfunction "VSS_31") (pintype "power_in"))
      (node (ref "DD1") (pin "41") (pinfunction "VSS_41") (pintype "power_in"))
      (node (ref "DD1") (pin "55") (pinfunction "VSS_55") (pintype "power_in"))
      (node (ref "DD1") (pin "72") (pinfunction "VSS_72") (pintype "power_in"))
      (node (ref "DD1") (pin "83") (pinfunction "VSS_83") (pintype "power_in"))
      (node (ref "DD1") (pin "97") (pinfunction "VSS_97") (pintype "power_in"))
      (node (ref "R10") (pin "2") (pintype "passive"))
      (node (ref "R16") (pin "2") (pintype "passive"))
      (node (ref "R17") (pin "2") (pintype "passive"))
      (node (ref "R21") (pin "1") (pintype "passive"))
      (node (ref "R3") (pin "1") (pintype "passive"))
      (node (ref "R4") (pin "2") (pintype "passive"))
      (node (ref "R5") (pin "2") (pintype "passive"))
      (node (ref "R9") (pin "2") (pintype "passive"))
      (node (ref "VD3") (pin "3") (pinfunction "A_3") (pintype "passive"))
      (node (ref "VT1") (pin "2") (pinfunction "S_2") (pintype "passive"))
      (node (ref "VT2") (pin "2") (pinfunction "S_2") (pintype "passive"))
      (node (ref "VT3") (pin "2") (pinfunction "S_2") (pintype "passive"))
      (node (ref "VT4") (pin "2") (pinfunction "S_2") (pintype "passive"))
      (node (ref "X2") (pin "3") (pinfunction "3_3") (pintype "passive"))
      (node (ref "X2") (pin "5") (pinfunction "5_5") (pintype "passive"))
      (node (ref "X2") (pin "9") (pinfunction "9_9") (pintype "passive"))
      (node (ref "X5") (pin "4") (pinfunction "4_4") (pintype "passive"))
      (node (ref "X5") (pin "6") (pinfunction "6_6") (pintype "passive"))
      (node (ref "X5") (pin "8") (pinfunction "8_8") (pintype "passive"))
    )
    (net (code "31") (name "GND_EXT") (class "Default")
      (node (ref "C1") (pin "2") (pinfunction "i/o1_2") (pintype "passive"))
      (node (ref "C3") (pin "2") (pinfunction "2_2") (pintype "passive"))
      (node (ref "C4") (pin "2") (pinfunction "2_2") (pintype "passive"))
      (node (ref "C5") (pin "2") (pinfunction "2_2") (pintype "passive"))
      (node (ref "DA1") (pin "2") (pinfunction "GND_2") (pintype "power_in"))
      (node (ref "DA2") (pin "5") (pinfunction "~{ON}/OFF_5") (pintype "input"))
      (node (ref "DA2") (pin "6") (pinfunction "GND_6") (pintype "power_in"))
      (node (ref "R2") (pin "2") (pintype "passive"))
      (node (ref "R3") (pin "2") (pintype "passive"))
      (node (ref "VD2") (pin "3") (pinfunction "A_3") (pintype "passive"))
      (node (ref "X4") (pin "4") (pinfunction "4_4") (pintype "passive"))
      (node (ref "X4") (pin "5") (pinfunction "5_5") (pintype "passive"))
      (node (ref "X5") (pin "14") (pinfunction "14_14") (pintype "passive"))
    )
    (net (code "32") (name "Net-(C9-Pad2)") (class "Default")
      (node (ref "C9") (pin "2") (pinfunction "2_2") (pintype "passive"))
      (node (ref "R11") (pin "1") (pintype "passive"))
      (node (ref "R12") (pin "1") (pintype "passive"))
      (node (ref "R6") (pin "1") (pintype "passive"))
      (node (ref "R8") (pin "1") (pintype "passive"))
    )
    (net (code "33") (name "Net-(DA1-NFB)") (class "Default")
      (node (ref "C2") (pin "2") (pinfunction "2_2") (pintype "passive"))
      (node (ref "DA1") (pin "3") (pinfunction "NFB_3") (pintype "input"))
      (node (ref "R1") (pin "2") (pintype "passive"))
      (node (ref "R2") (pin "1") (pintype "passive"))
    )
    (net (code "34") (name "Net-(DA1-SW)") (class "Default")
      (node (ref "DA1") (pin "1") (pinfunction "SW_1") (pintype "passive"))
      (node (ref "L2") (pin "2") (pinfunction "2_2") (pintype "passive"))
      (node (ref "VD1") (pin "3") (pinfunction "A_3") (pintype "passive"))
    )
    (net (code "35") (name "Net-(DA2-VOUT)") (class "Default")
      (node (ref "DA2") (pin "8") (pinfunction "VOUT_8") (pintype "power_in"))
      (node (ref "L1") (pin "1") (pinfunction "1_1") (pintype "passive"))
      (node (ref "VD2") (pin "1") (pinfunction "K1_1") (pintype "passive"))
      (node (ref "VD2") (pin "2") (pinfunction "K2_2") (pintype "passive"))
    )
    (net (code "36") (name "Net-(DA3-C1+)") (class "Default")
      (node (ref "C6") (pin "1") (pinfunction "1_1") (pintype "passive"))
      (node (ref "DA3") (pin "2") (pinfunction "C1+_2") (pintype "input"))
    )
    (net (code "37") (name "Net-(DA3-C1-)") (class "Default")
      (node (ref "C6") (pin "2") (pinfunction "2_2") (pintype "passive"))
      (node (ref "DA3") (pin "4") (pinfunction "C1-_4") (pintype "input"))
    )
    (net (code "38") (name "Net-(DA4A-INA-)") (class "Default")
      (node (ref "C13") (pin "1") (pinfunction "1_1") (pintype "passive"))
      (node (ref "DA4") (pin "2") (pinfunction "INA-_2") (pintype "input"))
      (node (ref "R13") (pin "1") (pintype "passive"))
      (node (ref "R14") (pin "2") (pintype "passive"))
    )
    (net (code "39") (name "Net-(DA4A-OUTA)") (class "Default")
      (node (ref "C13") (pin "2") (pinfunction "2_2") (pintype "passive"))
      (node (ref "DA4") (pin "1") (pinfunction "OUTA_1") (pintype "output"))
      (node (ref "R14") (pin "1") (pintype "passive"))
      (node (ref "R15") (pin "2") (pintype "passive"))
    )
    (net (code "40") (name "Net-(DA4B-INB-)") (class "Default")
      (node (ref "C9") (pin "1") (pinfunction "1_1") (pintype "passive"))
      (node (ref "DA4") (pin "6") (pinfunction "INB-_6") (pintype "input"))
      (node (ref "R4") (pin "1") (pintype "passive"))
      (node (ref "R6") (pin "2") (pintype "passive"))
    )
    (net (code "41") (name "Net-(HL1-K)") (class "Default")
      (node (ref "HL1") (pin "2") (pinfunction "K_2") (pintype "passive"))
      (node (ref "R16") (pin "1") (pintype "passive"))
    )
    (net (code "42") (name "Net-(HL2-K)") (class "Default")
      (node (ref "HL2") (pin "2") (pinfunction "K_2") (pintype "passive"))
      (node (ref "R17") (pin "1") (pintype "passive"))
    )
    (net (code "43") (name "Net-(VT1-D)") (class "Default")
      (node (ref "R11") (pin "2") (pintype "passive"))
      (node (ref "VT1") (pin "3") (pinfunction "D_3") (pintype "passive"))
    )
    (net (code "44") (name "Net-(VT2-D)") (class "Default")
      (node (ref "R12") (pin "2") (pintype "passive"))
      (node (ref "VT2") (pin "3") (pinfunction "D_3") (pintype "passive"))
    )
    (net (code "45") (name "Net-(VT3-D)") (class "Default")
      (node (ref "VT3") (pin "3") (pinfunction "D_3") (pintype "passive"))
      (node (ref "X4") (pin "6") (pinfunction "6_6") (pintype "passive"))
    )
    (net (code "46") (name "Net-(VT4-D)") (class "Default")
      (node (ref "VT4") (pin "3") (pinfunction "D_3") (pintype "passive"))
      (node (ref "X4") (pin "8") (pinfunction "8_8") (pintype "passive"))
    )
    (net (code "47") (name "Net-(X3-I{slash}O2)") (class "Default")
      (node (ref "X3") (pin "2") (pinfunction "I/O2_2") (pintype "passive"))
      (node (ref "X4") (pin "2") (pinfunction "2_2") (pintype "passive"))
    )
    (net (code "48") (name "unconnected-(DA2-NC-Pad1)") (class "Default")
      (node (ref "DA2") (pin "1") (pinfunction "NC_1") (pintype "passive"))
    )
    (net (code "49") (name "unconnected-(DA2-NC-Pad2)") (class "Default")
      (node (ref "DA2") (pin "2") (pinfunction "NC_2") (pintype "passive"))
    )
    (net (code "50") (name "unconnected-(DA2-NC-Pad3)") (class "Default")
      (node (ref "DA2") (pin "3") (pinfunction "NC_3") (pintype "passive"))
    )
    (net (code "51") (name "unconnected-(DA3-NC-Pad1)") (class "Default")
      (node (ref "DA3") (pin "1") (pinfunction "NC_1") (pintype "passive"))
    )
    (net (code "52") (name "unconnected-(DA3-OSC-Pad7)") (class "Default")
      (node (ref "DA3") (pin "7") (pinfunction "OSC_7") (pintype "input"))
    )
    (net (code "53") (name "unconnected-(DA4A-V+-Pad8)") (class "Default")
      (node (ref "DA4") (pin "8") (pinfunction "V+_8") (pintype "power_in"))
    )
    (net (code "54") (name "unconnected-(DA4A-V--Pad4)") (class "Default")
      (node (ref "DA4") (pin "4") (pinfunction "V-_4") (pintype "power_in"))
    )
    (net (code "55") (name "unconnected-(DA5-OSC_IN{slash}PD0-Pad5)") (class "Default")
      (node (ref "DA5") (pin "5") (pinfunction "OSC_IN/PD0_5") (pintype "input"))
    )
    (net (code "56") (name "unconnected-(DA5-OSC_OUT{slash}PD1-Pad6)") (class "Default")
      (node (ref "DA5") (pin "6") (pinfunction "OSC_OUT/PD1_6") (pintype "output"))
    )
    (net (code "57") (name "unconnected-(DA5-PA0-WKUP-Pad10)") (class "Default")
      (node (ref "DA5") (pin "10") (pinfunction "PA0-WKUP_10") (pintype "bidirectional"))
    )
    (net (code "58") (name "unconnected-(DA5-PA1-Pad11)") (class "Default")
      (node (ref "DA5") (pin "11") (pinfunction "PA1_11") (pintype "bidirectional"))
    )
    (net (code "59") (name "unconnected-(DA5-PA2-Pad12)") (class "Default")
      (node (ref "DA5") (pin "12") (pinfunction "PA2_12") (pintype "bidirectional"))
    )
    (net (code "60") (name "unconnected-(DA5-PA7-Pad17)") (class "Default")
      (node (ref "DA5") (pin "17") (pinfunction "PA7_17") (pintype "bidirectional"))
    )
    (net (code "61") (name "unconnected-(DA5-PA8-Pad29)") (class "Default")
      (node (ref "DA5") (pin "29") (pinfunction "PA8_29") (pintype "bidirectional"))
    )
    (net (code "62") (name "unconnected-(DA5-PB0-Pad18)") (class "Default")
      (node (ref "DA5") (pin "18") (pinfunction "PB0_18") (pintype "bidirectional"))
    )
    (net (code "63") (name "unconnected-(DA5-PB1-Pad19)") (class "Default")
      (node (ref "DA5") (pin "19") (pinfunction "PB1_19") (pintype "bidirectional"))
    )
    (net (code "64") (name "unconnected-(DA5-PB2{slash}BOOT1-Pad20)") (class "Default")
      (node (ref "DA5") (pin "20") (pinfunction "PB2/BOOT1_20") (pintype "bidirectional"))
    )
    (net (code "65") (name "unconnected-(DA5-PB6-Pad42)") (class "Default")
      (node (ref "DA5") (pin "42") (pinfunction "PB6_42") (pintype "bidirectional"))
    )
    (net (code "66") (name "unconnected-(DA5-PB7-Pad43)") (class "Default")
      (node (ref "DA5") (pin "43") (pinfunction "PB7_43") (pintype "bidirectional"))
    )
    (net (code "67") (name "unconnected-(DA5-PB10-Pad21)") (class "Default")
      (node (ref "DA5") (pin "21") (pinfunction "PB10_21") (pintype "bidirectional"))
    )
    (net (code "68") (name "unconnected-(DA5-PB11-Pad22)") (class "Default")
      (node (ref "DA5") (pin "22") (pinfunction "PB11_22") (pintype "bidirectional"))
    )
    (net (code "69") (name "unconnected-(DA5-PC13-TAMPER-RTC-Pad2)") (class "Default")
      (node (ref "DA5") (pin "2") (pinfunction "PC13-TAMPER-RTC_2") (pintype "bidirectional"))
    )
    (net (code "70") (name "unconnected-(DA5-PC14-OSC32_IN-Pad3)") (class "Default")
      (node (ref "DA5") (pin "3") (pinfunction "PC14-OSC32_IN_3") (pintype "bidirectional"))
    )
    (net (code "71") (name "unconnected-(DA5-PC15-OSC32_OUT-Pad4)") (class "Default")
      (node (ref "DA5") (pin "4") (pinfunction "PC15-OSC32_OUT_4") (pintype "bidirectional"))
    )
    (net (code "72") (name "unconnected-(DD1A-P0[2]{slash}TXD0-Pad98)") (class "Default")
      (node (ref "DD1") (pin "98") (pinfunction "P0[2]/TXD0_98") (pintype "bidirectional"))
    )
    (net (code "73") (name "unconnected-(DD1A-P0[3]{slash}RXD0-Pad99)") (class "Default")
      (node (ref "DD1") (pin "99") (pinfunction "P0[3]/RXD0_99") (pintype "bidirectional"))
    )
    (net (code "74") (name "unconnected-(DD1A-P0[4]{slash}I2SRX_CLK{slash}RD2{slash}CAP2[0]-Pad81)") (class "Default")
      (node (ref "DD1") (pin "81") (pinfunction "P0[4]/I2SRX_CLK/RD2/CAP2[0]_81") (pintype "bidirectional"))
    )
    (net (code "75") (name "unconnected-(DD1A-P0[6]{slash}I2SRX_SDA{slash}SSEL1{slash}MAT2[0]-Pad79)") (class "Default")
      (node (ref "DD1") (pin "79") (pinfunction "P0[6]/I2SRX_SDA/SSEL1/MAT2[0]_79") (pintype "bidirectional"))
    )
    (net (code "76") (name "unconnected-(DD1A-P0[7]{slash}I2STX_CLK{slash}SCK1{slash}MAT2[1]-Pad78)") (class "Default")
      (node (ref "DD1") (pin "78") (pinfunction "P0[7]/I2STX_CLK/SCK1/MAT2[1]_78") (pintype "bidirectional"))
    )
    (net (code "77") (name "unconnected-(DD1A-P0[8]{slash}I2STX_WS{slash}MISO1{slash}MAT2[2]-Pad77)") (class "Default")
      (node (ref "DD1") (pin "77") (pinfunction "P0[8]/I2STX_WS/MISO1/MAT2[2]_77") (pintype "bidirectional"))
    )
    (net (code "78") (name "unconnected-(DD1A-P0[9]{slash}I2STX_SDA{slash}MOSI1{slash}MAT2[3]-Pad76)") (class "Default")
      (node (ref "DD1") (pin "76") (pinfunction "P0[9]/I2STX_SDA/MOSI1/MAT2[3]_76") (pintype "bidirectional"))
    )
    (net (code "79") (name "unconnected-(DD1A-P0[10]{slash}TXD2{slash}SDA2{slash}MAT3[0]-Pad48)") (class "Default")
      (node (ref "DD1") (pin "48") (pinfunction "P0[10]/TXD2/SDA2/MAT3[0]_48") (pintype "bidirectional"))
    )
    (net (code "80") (name "unconnected-(DD1A-P0[11]{slash}RXD2{slash}SCL2{slash}MAT3[1]-Pad49)") (class "Default")
      (node (ref "DD1") (pin "49") (pinfunction "P0[11]/RXD2/SCL2/MAT3[1]_49") (pintype "bidirectional"))
    )
    (net (code "81") (name "unconnected-(DD1A-P0[15]{slash}TXD1{slash}SCK0{slash}SCK-Pad62)") (class "Default")
      (node (ref "DD1") (pin "62") (pinfunction "P0[15]/TXD1/SCK0/SCK_62") (pintype "bidirectional"))
    )
    (net (code "82") (name "unconnected-(DD1A-P0[16]{slash}RXD1{slash}SSEL0{slash}SSEL-Pad63)") (class "Default")
      (node (ref "DD1") (pin "63") (pinfunction "P0[16]/RXD1/SSEL0/SSEL_63") (pintype "bidirectional"))
    )
    (net (code "83") (name "unconnected-(DD1A-P0[17]{slash}CTS1{slash}MISO0{slash}MISO-Pad61)") (class "Default")
      (node (ref "DD1") (pin "61") (pinfunction "P0[17]/CTS1/MISO0/MISO_61") (pintype "bidirectional"))
    )
    (net (code "84") (name "unconnected-(DD1A-P0[18]{slash}DCD1{slash}MOSI0{slash}MOSI-Pad60)") (class "Default")
      (node (ref "DD1") (pin "60") (pinfunction "P0[18]/DCD1/MOSI0/MOSI_60") (pintype "bidirectional"))
    )
    (net (code "85") (name "unconnected-(DD1A-P0[19]{slash}DSR1{slash}MCICLK{slash}SDA1-Pad59)") (class "Default")
      (node (ref "DD1") (pin "59") (pinfunction "P0[19]/DSR1/MCICLK/SDA1_59") (pintype "bidirectional"))
    )
    (net (code "86") (name "unconnected-(DD1A-P0[20]{slash}DTR1{slash}MCICMD{slash}SCL1-Pad58)") (class "Default")
      (node (ref "DD1") (pin "58") (pinfunction "P0[20]/DTR1/MCICMD/SCL1_58") (pintype "bidirectional"))
    )
    (net (code "87") (name "unconnected-(DD1A-P0[21]{slash}RI1{slash}MCIPWR{slash}RD1-Pad57)") (class "Default")
      (node (ref "DD1") (pin "57") (pinfunction "P0[21]/RI1/MCIPWR/RD1_57") (pintype "bidirectional"))
    )
    (net (code "88") (name "unconnected-(DD1A-P0[22]{slash}RTS1{slash}MCIDAT0{slash}TD1-Pad56)") (class "Default")
      (node (ref "DD1") (pin "56") (pinfunction "P0[22]/RTS1/MCIDAT0/TD1_56") (pintype "bidirectional"))
    )
    (net (code "89") (name "unconnected-(DD1A-P0[27]{slash}SDA0-Pad25)") (class "Default")
      (node (ref "DD1") (pin "25") (pinfunction "P0[27]/SDA0_25") (pintype "bidirectional"))
    )
    (net (code "90") (name "unconnected-(DD1A-P0[28]{slash}SCL0-Pad24)") (class "Default")
      (node (ref "DD1") (pin "24") (pinfunction "P0[28]/SCL0_24") (pintype "bidirectional"))
    )
    (net (code "91") (name "unconnected-(DD1A-P0[29]{slash}USB_D+-Pad29)") (class "Default")
      (node (ref "DD1") (pin "29") (pinfunction "P0[29]/USB_D+_29") (pintype "bidirectional"))
    )
    (net (code "92") (name "unconnected-(DD1A-P0[30]{slash}USB_D--Pad30)") (class "Default")
      (node (ref "DD1") (pin "30") (pinfunction "P0[30]/USB_D-_30") (pintype "bidirectional"))
    )
    (net (code "93") (name "unconnected-(DD1A-P1[0]{slash}ENET_TXD0-Pad95)") (class "Default")
      (node (ref "DD1") (pin "95") (pinfunction "P1[0]/ENET_TXD0_95") (pintype "bidirectional"))
    )
    (net (code "94") (name "unconnected-(DD1A-P1[1]{slash}ENET_TXD1-Pad94)") (class "Default")
      (node (ref "DD1") (pin "94") (pinfunction "P1[1]/ENET_TXD1_94") (pintype "bidirectional"))
    )
    (net (code "95") (name "unconnected-(DD1A-P1[4]{slash}ENET_TX_EN-Pad93)") (class "Default")
      (node (ref "DD1") (pin "93") (pinfunction "P1[4]/ENET_TX_EN_93") (pintype "bidirectional"))
    )
    (net (code "96") (name "unconnected-(DD1A-P1[8]{slash}ENET_CRS-Pad92)") (class "Default")
      (node (ref "DD1") (pin "92") (pinfunction "P1[8]/ENET_CRS_92") (pintype "bidirectional"))
    )
    (net (code "97") (name "unconnected-(DD1A-P1[9]{slash}ENET_RXD0-Pad91)") (class "Default")
      (node (ref "DD1") (pin "91") (pinfunction "P1[9]/ENET_RXD0_91") (pintype "bidirectional"))
    )
    (net (code "98") (name "unconnected-(DD1A-P1[10]{slash}ENET_RXD1-Pad90)") (class "Default")
      (node (ref "DD1") (pin "90") (pinfunction "P1[10]/ENET_RXD1_90") (pintype "bidirectional"))
    )
    (net (code "99") (name "unconnected-(DD1A-P1[14]{slash}ENET_RX_ER-Pad89)") (class "Default")
      (node (ref "DD1") (pin "89") (pinfunction "P1[14]/ENET_RX_ER_89") (pintype "bidirectional"))
    )
    (net (code "100") (name "unconnected-(DD1A-P1[15]{slash}ENET_REF_CLK-Pad88)") (class "Default")
      (node (ref "DD1") (pin "88") (pinfunction "P1[15]/ENET_REF_CLK_88") (pintype "bidirectional"))
    )
    (net (code "101") (name "unconnected-(DD1A-P1[16]{slash}ENET_MDC-Pad87)") (class "Default")
      (node (ref "DD1") (pin "87") (pinfunction "P1[16]/ENET_MDC_87") (pintype "bidirectional"))
    )
    (net (code "102") (name "unconnected-(DD1A-P1[17]{slash}ENET_MDIO-Pad86)") (class "Default")
      (node (ref "DD1") (pin "86") (pinfunction "P1[17]/ENET_MDIO_86") (pintype "bidirectional"))
    )
    (net (code "103") (name "unconnected-(DD1A-P1[22]{slash}MAT1[0]-Pad36)") (class "Default")
      (node (ref "DD1") (pin "36") (pinfunction "P1[22]/MAT1[0]_36") (pintype "bidirectional"))
    )
    (net (code "104") (name "unconnected-(DD1A-P1[23]{slash}PWM1[4]{slash}MISO0-Pad37)") (class "Default")
      (node (ref "DD1") (pin "37") (pinfunction "P1[23]/PWM1[4]/MISO0_37") (pintype "bidirectional"))
    )
    (net (code "105") (name "unconnected-(DD1A-P1[24]{slash}PWM1[5]{slash}MOSI0-Pad38)") (class "Default")
      (node (ref "DD1") (pin "38") (pinfunction "P1[24]/PWM1[5]/MOSI0_38") (pintype "bidirectional"))
    )
    (net (code "106") (name "unconnected-(DD1A-P1[27]{slash}CAP0[1]-Pad43)") (class "Default")
      (node (ref "DD1") (pin "43") (pinfunction "P1[27]/CAP0[1]_43") (pintype "bidirectional"))
    )
    (net (code "107") (name "unconnected-(DD1A-P1[28]{slash}PCAP1[0]{slash}MAT0[0]-Pad44)") (class "Default")
      (node (ref "DD1") (pin "44") (pinfunction "P1[28]/PCAP1[0]/MAT0[0]_44") (pintype "bidirectional"))
    )
    (net (code "108") (name "unconnected-(DD1A-P1[29]{slash}PCAP1[1]{slash}MAT0[1]-Pad45)") (class "Default")
      (node (ref "DD1") (pin "45") (pinfunction "P1[29]/PCAP1[1]/MAT0[1]_45") (pintype "bidirectional"))
    )
    (net (code "109") (name "unconnected-(DD1A-P1[30]{slash}VBUS{slash}AD0[4]-Pad21)") (class "Default")
      (node (ref "DD1") (pin "21") (pinfunction "P1[30]/VBUS/AD0[4]_21") (pintype "bidirectional"))
    )
    (net (code "110") (name "unconnected-(DD1A-P1[31]{slash}SCK1{slash}AD0[5]-Pad20)") (class "Default")
      (node (ref "DD1") (pin "20") (pinfunction "P1[31]/SCK1/AD0[5]_20") (pintype "bidirectional"))
    )
    (net (code "111") (name "unconnected-(DD1A-P2[0]{slash}PWM1[1]{slash}TXD1{slash}TRACECLK-Pad75)") (class "Default")
      (node (ref "DD1") (pin "75") (pinfunction "P2[0]/PWM1[1]/TXD1/TRACECLK_75") (pintype "bidirectional"))
    )
    (net (code "112") (name "unconnected-(DD1A-P2[1]{slash}PWM1[2]{slash}RXD1{slash}PIPESTAT0-Pad74)") (class "Default")
      (node (ref "DD1") (pin "74") (pinfunction "P2[1]/PWM1[2]/RXD1/PIPESTAT0_74") (pintype "bidirectional"))
    )
    (net (code "113") (name "unconnected-(DD1A-P2[2]{slash}PWM1[3]{slash}CTS1{slash}PIPESTAT1-Pad73)") (class "Default")
      (node (ref "DD1") (pin "73") (pinfunction "P2[2]/PWM1[3]/CTS1/PIPESTAT1_73") (pintype "bidirectional"))
    )
    (net (code "114") (name "unconnected-(DD1A-P2[6]{slash}PCAP1[0]{slash}RI1{slash}TRACEPKT1-Pad67)") (class "Default")
      (node (ref "DD1") (pin "67") (pinfunction "P2[6]/PCAP1[0]/RI1/TRACEPKT1_67") (pintype "bidirectional"))
    )
    (net (code "115") (name "unconnected-(DD1A-P2[7]{slash}RD2{slash}RTS1{slash}TRACEPKT2-Pad66)") (class "Default")
      (node (ref "DD1") (pin "66") (pinfunction "P2[7]/RD2/RTS1/TRACEPKT2_66") (pintype "bidirectional"))
    )
    (net (code "116") (name "unconnected-(DD1A-P2[8]{slash}TD2{slash}TXD2{slash}TRACEPKT3-Pad65)") (class "Default")
      (node (ref "DD1") (pin "65") (pinfunction "P2[8]/TD2/TXD2/TRACEPKT3_65") (pintype "bidirectional"))
    )
    (net (code "117") (name "unconnected-(DD1A-P2[9]{slash}USB_CONNECT{slash}RXD2{slash}EXTIN0-Pad64)") (class "Default")
      (node (ref "DD1") (pin "64") (pinfunction "P2[9]/USB_CONNECT/RXD2/EXTIN0_64") (pintype "bidirectional"))
    )
    (net (code "118") (name "unconnected-(DD1A-P2[10]{slash}~{EINT}0-Pad53)") (class "Default")
      (node (ref "DD1") (pin "53") (pinfunction "P2[10]/~{EINT}0_53") (pintype "bidirectional"))
    )
    (net (code "119") (name "unconnected-(DD1A-P2[11]{slash}~{EINT}1{slash}MCIDAT1{slash}I2STX_CLK-Pad52)") (class "Default")
      (node (ref "DD1") (pin "52") (pinfunction "P2[11]/~{EINT}1/MCIDAT1/I2STX_CLK_52") (pintype "bidirectional"))
    )
    (net (code "120") (name "unconnected-(DD1A-P2[12]{slash}~{EINT}2{slash}MCIDAT2{slash}I2STX_WS-Pad51)") (class "Default")
      (node (ref "DD1") (pin "51") (pinfunction "P2[12]/~{EINT}2/MCIDAT2/I2STX_WS_51") (pintype "bidirectional"))
    )
    (net (code "121") (name "unconnected-(DD1A-P2[13]{slash}~{EINT}3{slash}MCIDAT3{slash}I2STX_SDA-Pad50)") (class "Default")
      (node (ref "DD1") (pin "50") (pinfunction "P2[13]/~{EINT}3/MCIDAT3/I2STX_SDA_50") (pintype "bidirectional"))
    )
    (net (code "122") (name "unconnected-(DD1A-P3[25]{slash}MAT0[0]{slash}PWM1[2]-Pad27)") (class "Default")
      (node (ref "DD1") (pin "27") (pinfunction "P3[25]/MAT0[0]/PWM1[2]_27") (pintype "bidirectional"))
    )
    (net (code "123") (name "unconnected-(DD1A-P3[26]{slash}MAT0[1]{slash}PWM1[3]-Pad26)") (class "Default")
      (node (ref "DD1") (pin "26") (pinfunction "P3[26]/MAT0[1]/PWM1[3]_26") (pintype "bidirectional"))
    )
    (net (code "124") (name "unconnected-(DD1A-P4[28]{slash}MAT2[0]{slash}TXD3-Pad82)") (class "Default")
      (node (ref "DD1") (pin "82") (pinfunction "P4[28]/MAT2[0]/TXD3_82") (pintype "bidirectional"))
    )
    (net (code "125") (name "unconnected-(DD1A-P4[29]{slash}MAT2[1]{slash}RXD3-Pad85)") (class "Default")
      (node (ref "DD1") (pin "85") (pinfunction "P4[29]/MAT2[1]/RXD3_85") (pintype "bidirectional"))
    )
    (net (code "126") (name "unconnected-(DD1B-RTCK-Pad100)") (class "Default")
      (node (ref "DD1") (pin "100") (pinfunction "RTCK_100") (pintype "bidirectional"))
    )
    (net (code "127") (name "unconnected-(DD1B-~{TRST}-Pad4)") (class "Default")
      (node (ref "DD1") (pin "4") (pinfunction "~{TRST}_4") (pintype "input"))
    )
    (net (code "128") (name "unconnected-(DD1C-RTCX1-Pad16)") (class "Default")
      (node (ref "DD1") (pin "16") (pinfunction "RTCX1_16") (pintype "input"))
    )
    (net (code "129") (name "unconnected-(DD1C-RTCX2-Pad18)") (class "Default")
      (node (ref "DD1") (pin "18") (pinfunction "RTCX2_18") (pintype "output"))
    )
    (net (code "130") (name "unconnected-(DD1C-XTAL1-Pad22)") (class "Default")
      (node (ref "DD1") (pin "22") (pinfunction "XTAL1_22") (pintype "input"))
    )
    (net (code "131") (name "unconnected-(DD1C-XTAL2-Pad23)") (class "Default")
      (node (ref "DD1") (pin "23") (pinfunction "XTAL2_23") (pintype "output"))
    )
    (net (code "132") (name "unconnected-(DD1C-~{RSTOUT}-Pad14)") (class "Default")
      (node (ref "DD1") (pin "14") (pinfunction "~{RSTOUT}_14") (pintype "output"))
    )
    (net (code "133") (name "unconnected-(X2-Pad7)") (class "Default")
      (node (ref "X2") (pin "7") (pinfunction "7_7") (pintype "passive"))
    )
  )
)
